# Gas_leakage.net
KiCad netlist of a schematic drawn in Altium Designer
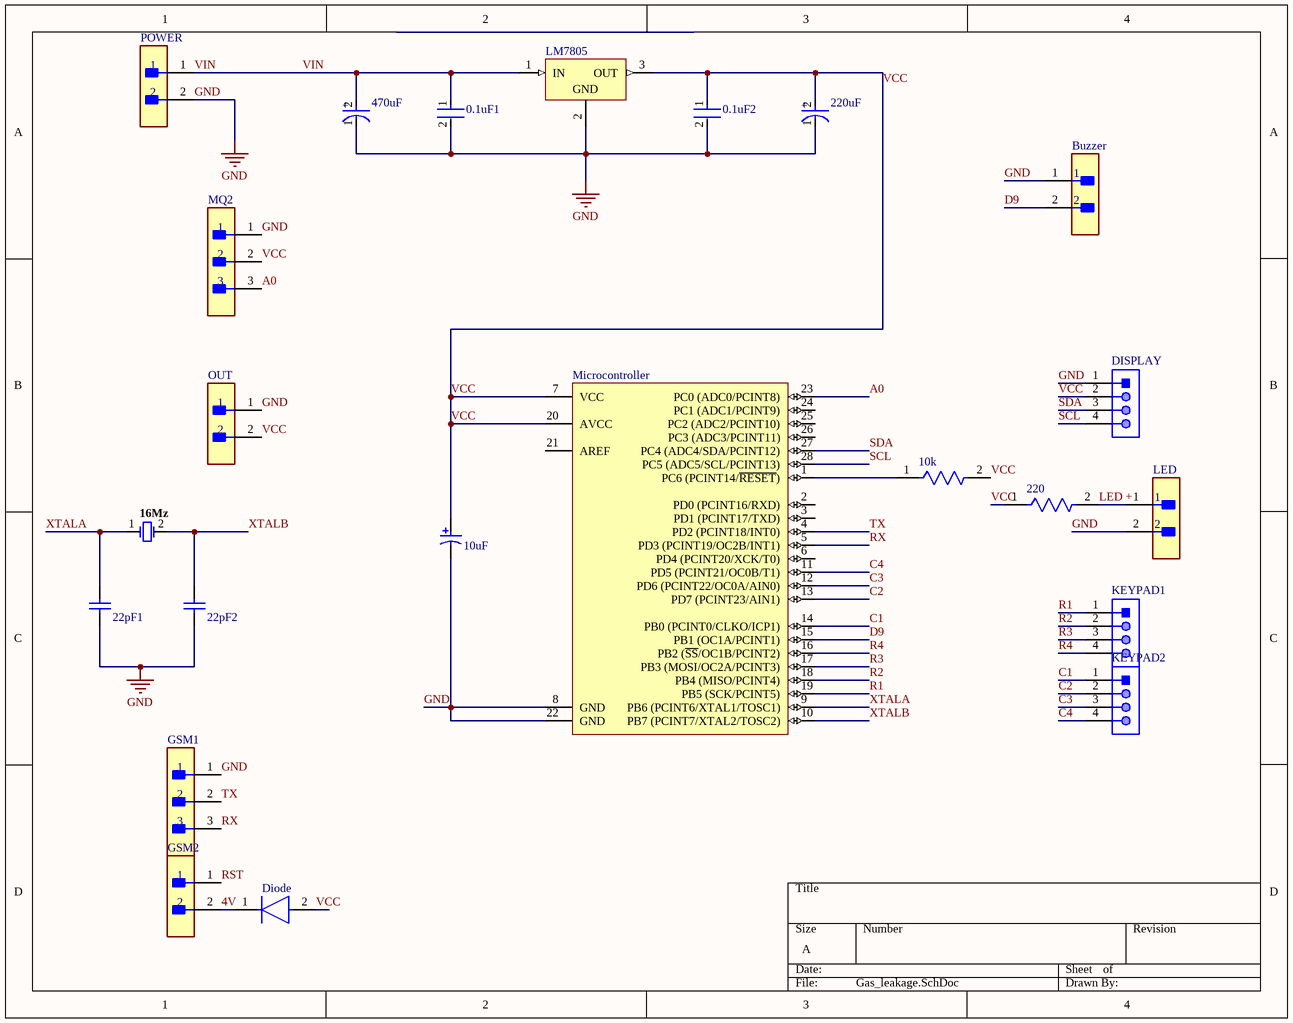
[diagram p0: Gas_leakage.SchDoc]

(export (version "E")
  (design (tool "Eeschema 10.0.6"))
  (components
    (comp (ref "0.1uF1")
      (value "SR205C104KAR")
      (footprint "FP-SR20-MFG")
      (description "CAP CER 0.1UF 50V X7R RADIAL")
      (fields (field (name "VOLTAGE") "50V") (field (name "TOLERANCE") "10%"))
      (libsource (lib "Altium Content Vault") (part "11868f565c42a9108669ba33697ecf6"))
    )
    (comp (ref "0.1uF2")
      (value "SR205C104KAR")
      (footprint "FP-SR20-MFG")
      (description "CAP CER 0.1UF 50V X7R RADIAL")
      (fields (field (name "VOLTAGE") "50V") (field (name "TOLERANCE") "10%"))
      (libsource (lib "Altium Content Vault") (part "11868f565c42a9108669ba33697ecf6"))
    )
    (comp (ref "10k")
      (value "CF18JT10K0")
      (footprint "FP-CF18-MFG")
      (description "RES 10K OHM 1/8W 5% CF AXIAL")
      (fields
        (field (name "MANUFACTURER") "Stackpole Electronics")
        (field (name "OCTOPART") "https://octopart.com/cf18jt10k0-stackpole+electronics-19205642")
      )
      (libsource (lib "Altium Content Vault") (part "1029c3af85768c4190bb7ad29bc67b5"))
    )
    (comp (ref "10uF")
      (value "ECA1HM100")
      (footprint "CAPPR55-200-1100X500X1200")
      (description "Aluminum Electrolytic Capacitor, 10 uF, +/- 20%, 50 V, -40 to 85 degC, 2-Pin THD, RoHS, Bulk")
      (fields (field (name "MANUFACTURER") "Panasonic") (field (name "TOLERANCE") "20%"))
      (libsource (lib "Altium Content Vault") (part "CAP-P-2"))
    )
    (comp (ref "16Mz")
      (value "FOXSLF/160-20")
      (footprint "FOX-FOXSLF160-20")
      (description "Resistance Weld Thru-Hole Crystal, 16 MHz, -20 to 70 degC, 2-Pin THD, RoHS, Bulk")
      (fields (field (name "TOLERANCE") "1%"))
      (libsource (lib "Altium Content Vault") (part "XTAL-1-2-2"))
    )
    (comp (ref "22pF1")
      (value "C315C220K1G5TA")
      (footprint "KEMT-C315-THT-2")
      (description "Capacitor, Ceramic, 22 pF, +/-10 %, 100 V, -55 to 125 degC, 2-Pin THD, RoHS, Bulk")
      (libsource (lib "Altium Content Vault") (part "CAP-NP-2"))
    )
    (comp (ref "22pF2")
      (value "C315C220K1G5TA")
      (footprint "KEMT-C315-THT-2")
      (description "Capacitor, Ceramic, 22 pF, +/-10 %, 100 V, -55 to 125 degC, 2-Pin THD, RoHS, Bulk")
      (libsource (lib "Altium Content Vault") (part "CAP-NP-2"))
    )
    (comp (ref "220")
      (value "CMF55205R00FHEB")
      (footprint "FP-CMF55-MFG")
      (description "RES 220 OHM 1/2W 1% AXIAL")
      (fields (field (name "TOLERANCE") "1%"))
      (libsource (lib "Altium Content Vault") (part "1029c3af85768c4190bb7ad29bc67b5"))
    )
    (comp (ref "220uF")
      (value "EEUFM1A221")
      (footprint "FP-RAD-TH-D_6_3_0_5-L_11-MFG")
      (description "Aluminum Electrolytic Capacitors (Radial Lead Type) 220uF ±20% 10V")
      (fields (field (name "VOLTAGE") "10V") (field (name "TOLERANCE") "20%"))
      (libsource (lib "Altium Content Vault") (part "a00bbbee19879c290e62620ae7e47b1"))
    )
    (comp (ref "470uF")
      (value "EEUHD1E471")
      (footprint "FP-RAD-TH-D_10_0_5-L_12_5-MFG")
      (description "Aluminum Electrolytic Capacitors (Radial Lead Type) AEC-Q200 Qualified 470uF ±20% 25V")
      (fields (field (name "TOLERANCE") "20%") (field (name "VOLTAGE") "25V"))
      (libsource (lib "Altium Content Vault") (part "203bc49f2ac43e59fd269a8c329ed05"))
    )
    (comp (ref "Buzzer")
      (value "M20-9990246")
      (footprint "FP-M20-9990246-MFG")
      (description "CONN HEADER VERT 2POS 2.54MM")
      (fields
        (field (name "OCTOPART") "https://octopart.com/m20-9990246-harwin-2590635")
        (field (name "MANUFACTURER") "Harwin")
      )
      (libsource (lib "") (part "3bc925449376181038e59eaffc5286c_1"))
    )
    (comp (ref "Diode")
      (value "1N5408G-T")
      (footprint "FP-DO-201AD-MFG")
      (description "DIODE GEN PURP 1KV 3A DO201AD")
      (libsource (lib "Altium Content Vault") (part "d7152d700b627762746794eb795d46e"))
    )
    (comp (ref "DISPLAY")
      (value "61300411121")
      (footprint "61300411121")
      (description "THT Vertical Pin Header WR-PHD, Pitch 2.54 mm, Single Row, 4 pins")
      (fields (field (name "MANUFACTURER") "Wurth Elektronik") (field (name "PUBLISHER") "WurthElektronik"))
      (libsource (lib "Altium Content Vault") (part "WE-CN-1P-M-R4"))
    )
    (comp (ref "GSM1")
      (value "90120-0763")
      (footprint "FP-90120-0763-MFG")
      (description "CONN HEADER VERT 3POS 2.54MM")
      (fields
        (field (name "MANUFACTURER") "Molex")
        (field (name "OCTOPART") "https://octopart.com/90120-0763-molex-655433")
      )
      (libsource (lib "Altium Content Vault") (part "0d3f023dd272f625e17a2be33dea85f"))
    )
    (comp (ref "GSM2")
      (value "M20-9990246")
      (footprint "FP-M20-9990246-MFG")
      (description "CONN HEADER VERT 2POS 2.54MM")
      (fields
        (field (name "OCTOPART") "https://octopart.com/m20-9990246-harwin-2590635")
        (field (name "MANUFACTURER") "Harwin")
      )
      (libsource (lib "Altium Content Vault") (part "3bc925449376181038e59eaffc5286c"))
    )
    (comp (ref "KEYPAD1")
      (value "1300411121")
      (footprint "61300411121")
      (description "THT Vertical Pin Header WR-PHD, Pitch 2.54 mm, Single Row, 4 pins")
      (fields
        (field (name "MANUFACTURER") "Wurth Elektronik")
        (field (name "PART NUMBER") "61300411121")
        (field (name "PUBLISHER") "WurthElektronik")
      )
      (libsource (lib "Altium Content Vault") (part "WE-CN-1P-M-R4"))
    )
    (comp (ref "KEYPAD2")
      (value "61300411121")
      (footprint "61300411121")
      (description "THT Vertical Pin Header WR-PHD, Pitch 2.54 mm, Single Row, 4 pins")
      (fields (field (name "MANUFACTURER") "Wurth Elektronik") (field (name "PUBLISHER") "WurthElektronik"))
      (libsource (lib "Altium Content Vault") (part "WE-CN-1P-M-R4"))
    )
    (comp (ref "LED")
      (value "M20-9990246")
      (footprint "FP-M20-9990246-MFG")
      (description "CONN HEADER VERT 2POS 2.54MM")
      (fields
        (field (name "OCTOPART") "https://octopart.com/m20-9990246-harwin-2590635")
        (field (name "MANUFACTURER") "Harwin")
      )
      (libsource (lib "") (part "3bc925449376181038e59eaffc5286c_1"))
    )
    (comp (ref "LM7805")
      (value "LM7805CT")
      (footprint "FAIR-TO-220-3")
      (description "Positive Voltage Regulator, 5 V, 1 A, -40 to 125 degC, 3-Pin TO-220, RoHS, Tube")
      (fields (field (name "MANUFACTURER") "FairchildSemiconductor"))
      (libsource (lib "Altium Content Vault") (part "FAIR-LM7805CT-TO220-3"))
    )
    (comp (ref "Microcontroller")
      (value "ATmega328P-PU")
      (footprint "28P3")
      (libsource (lib "Altium Content Vault") (part "MC-8B-ATM48-IL28"))
    )
    (comp (ref "MQ2")
      (value "90120-0763")
      (footprint "FP-90120-0763-MFG")
      (description "CONN HEADER VERT 3POS 2.54MM")
      (fields
        (field (name "MANUFACTURER") "Molex")
        (field (name "OCTOPART") "https://octopart.com/90120-0763-molex-655433")
      )
      (libsource (lib "Altium Content Vault") (part "0d3f023dd272f625e17a2be33dea85f"))
    )
    (comp (ref "OUT")
      (value "M20-9990246")
      (footprint "FP-M20-9990246-MFG")
      (description "CONN HEADER VERT 2POS 2.54MM")
      (fields
        (field (name "OCTOPART") "https://octopart.com/m20-9990246-harwin-2590635")
        (field (name "MANUFACTURER") "Harwin")
      )
      (libsource (lib "Altium Content Vault") (part "3bc925449376181038e59eaffc5286c"))
    )
    (comp (ref "POWER")
      (value "M20-9990246")
      (footprint "FP-M20-9990246-MFG")
      (description "CONN HEADER VERT 2POS 2.54MM")
      (fields
        (field (name "OCTOPART") "https://octopart.com/m20-9990246-harwin-2590635")
        (field (name "MANUFACTURER") "Harwin")
      )
      (libsource (lib "Altium Content Vault") (part "3bc925449376181038e59eaffc5286c"))
    )
  )
  (nets
    (net (code "1") (name "/4V") (class "Default")
      (node (ref "Diode") (pin "1") (pinfunction "C_1") (pintype "passive"))
      (node (ref "GSM2") (pin "2") (pinfunction "2_2") (pintype "passive"))
    )
    (net (code "2") (name "/A0") (class "Default")
      (node (ref "MQ2") (pin "3") (pinfunction "3_3") (pintype "passive"))
      (node (ref "Microcontroller") (pin "23") (pinfunction "PC0_(ADC0/PCINT8)_23") (pintype "bidirectional"))
    )
    (net (code "3") (name "/C1") (class "Default")
      (node (ref "KEYPAD2") (pin "1") (pinfunction "1_1") (pintype "passive"))
      (node (ref "Microcontroller") (pin "14") (pinfunction "PB0_(PCINT0/CLKO/ICP1)_14") (pintype "bidirectional"))
    )
    (net (code "4") (name "/C2") (class "Default")
      (node (ref "KEYPAD2") (pin "2") (pinfunction "2_2") (pintype "passive"))
      (node (ref "Microcontroller") (pin "13") (pinfunction "PD7_(PCINT23/AIN1)_13") (pintype "bidirectional"))
    )
    (net (code "5") (name "/C3") (class "Default")
      (node (ref "KEYPAD2") (pin "3") (pinfunction "3_3") (pintype "passive"))
      (node (ref "Microcontroller") (pin "12") (pinfunction "PD6_(PCINT22/OC0A/AIN0)_12") (pintype "bidirectional"))
    )
    (net (code "6") (name "/C4") (class "Default")
      (node (ref "KEYPAD2") (pin "4") (pinfunction "4_4") (pintype "passive"))
      (node (ref "Microcontroller") (pin "11") (pinfunction "PD5_(PCINT21/OC0B/T1)_11") (pintype "bidirectional"))
    )
    (net (code "7") (name "/D9") (class "Default")
      (node (ref "Buzzer") (pin "2") (pinfunction "2_2") (pintype "passive"))
      (node (ref "Microcontroller") (pin "15") (pinfunction "PB1_(OC1A/PCINT1)_15") (pintype "bidirectional"))
    )
    (net (code "8") (name "/LED +") (class "Default")
      (node (ref "220") (pin "2") (pinfunction "2_2") (pintype "passive"))
      (node (ref "LED") (pin "1") (pinfunction "1_1") (pintype "passive"))
    )
    (net (code "9") (name "/R1") (class "Default")
      (node (ref "KEYPAD1") (pin "1") (pinfunction "1_1") (pintype "passive"))
      (node (ref "Microcontroller") (pin "19") (pinfunction "PB5_(SCK/PCINT5)_19") (pintype "bidirectional"))
    )
    (net (code "10") (name "/R2") (class "Default")
      (node (ref "KEYPAD1") (pin "2") (pinfunction "2_2") (pintype "passive"))
      (node (ref "Microcontroller") (pin "18") (pinfunction "PB4_(MISO/PCINT4)_18") (pintype "bidirectional"))
    )
    (net (code "11") (name "/R3") (class "Default")
      (node (ref "KEYPAD1") (pin "3") (pinfunction "3_3") (pintype "passive"))
      (node (ref "Microcontroller") (pin "17") (pinfunction "PB3_(MOSI/OC2A/PCINT3)_17") (pintype "bidirectional"))
    )
    (net (code "12") (name "/R4") (class "Default")
      (node (ref "KEYPAD1") (pin "4") (pinfunction "4_4") (pintype "passive"))
      (node (ref "Microcontroller") (pin "16") (pinfunction "PB2_(~{SS}/OC1B/PCINT2)_16") (pintype "bidirectional"))
    )
    (net (code "13") (name "/RST") (class "Default")
      (node (ref "GSM2") (pin "1") (pinfunction "1_1") (pintype "passive"))
    )
    (net (code "14") (name "/RX") (class "Default")
      (node (ref "GSM1") (pin "3") (pinfunction "3_3") (pintype "passive"))
      (node (ref "Microcontroller") (pin "5") (pinfunction "PD3_(PCINT19/OC2B/INT1)_5") (pintype "bidirectional"))
    )
    (net (code "15") (name "/SCL") (class "Default")
      (node (ref "DISPLAY") (pin "4") (pinfunction "4_4") (pintype "passive"))
      (node (ref "Microcontroller") (pin "28") (pinfunction "PC5_(ADC5/SCL/PCINT13)_28") (pintype "bidirectional"))
    )
    (net (code "16") (name "/SDA") (class "Default")
      (node (ref "DISPLAY") (pin "3") (pinfunction "3_3") (pintype "passive"))
      (node (ref "Microcontroller") (pin "27") (pinfunction "PC4_(ADC4/SDA/PCINT12)_27") (pintype "bidirectional"))
    )
    (net (code "17") (name "/TX") (class "Default")
      (node (ref "GSM1") (pin "2") (pinfunction "2_2") (pintype "passive"))
      (node (ref "Microcontroller") (pin "4") (pinfunction "PD2_(PCINT18/INT0)_4") (pintype "bidirectional"))
    )
    (net (code "18") (name "/VCC") (class "Default")
      (node (ref "0.1uF2") (pin "1") (pinfunction "1_1") (pintype "passive"))
      (node (ref "10k") (pin "2") (pinfunction "2_2") (pintype "passive"))
      (node (ref "10uF") (pin "1") (pinfunction "1_1") (pintype "passive"))
      (node (ref "220") (pin "1") (pinfunction "1_1") (pintype "passive"))
      (node (ref "220uF") (pin "2") (pinfunction "A_2") (pintype "passive"))
      (node (ref "DISPLAY") (pin "2") (pinfunction "2_2") (pintype "passive"))
      (node (ref "Diode") (pin "2") (pinfunction "A_2") (pintype "passive"))
      (node (ref "LM7805") (pin "3") (pinfunction "OUT_3") (pintype "output"))
      (node (ref "MQ2") (pin "2") (pinfunction "2_2") (pintype "passive"))
      (node (ref "Microcontroller") (pin "20") (pinfunction "AVCC_20") (pintype "power_in"))
      (node (ref "Microcontroller") (pin "7") (pinfunction "VCC_7") (pintype "power_in"))
      (node (ref "OUT") (pin "2") (pinfunction "2_2") (pintype "passive"))
    )
    (net (code "19") (name "/VIN") (class "Default")
      (node (ref "0.1uF1") (pin "1") (pinfunction "1_1") (pintype "passive"))
      (node (ref "470uF") (pin "2") (pinfunction "A_2") (pintype "passive"))
      (node (ref "LM7805") (pin "1") (pinfunction "IN_1") (pintype "input"))
      (node (ref "POWER") (pin "1") (pinfunction "1_1") (pintype "passive"))
    )
    (net (code "20") (name "/XTALA") (class "Default")
      (node (ref "16Mz") (pin "1") (pinfunction "1_1") (pintype "passive"))
      (node (ref "22pF1") (pin "2") (pinfunction "2_2") (pintype "passive"))
      (node (ref "Microcontroller") (pin "9") (pinfunction "PB6_(PCINT6/XTAL1/TOSC1)_9") (pintype "bidirectional"))
    )
    (net (code "21") (name "/XTALB") (class "Default")
      (node (ref "16Mz") (pin "2") (pinfunction "2_2") (pintype "passive"))
      (node (ref "22pF2") (pin "2") (pinfunction "2_2") (pintype "passive"))
      (node (ref "Microcontroller") (pin "10") (pinfunction "PB7_(PCINT7/XTAL2/TOSC2)_10") (pintype "bidirectional"))
    )
    (net (code "22") (name "GND") (class "Default")
      (node (ref "0.1uF1") (pin "2") (pinfunction "2_2") (pintype "passive"))
      (node (ref "0.1uF2") (pin "2") (pinfunction "2_2") (pintype "passive"))
      (node (ref "10uF") (pin "2") (pinfunction "2_2") (pintype "passive"))
      (node (ref "220uF") (pin "1") (pinfunction "C_1") (pintype "passive"))
      (node (ref "22pF1") (pin "1") (pinfunction "1_1") (pintype "passive"))
      (node (ref "22pF2") (pin "1") (pinfunction "1_1") (pintype "passive"))
      (node (ref "470uF") (pin "1") (pinfunction "C_1") (pintype "passive"))
      (node (ref "Buzzer") (pin "1") (pinfunction "1_1") (pintype "passive"))
      (node (ref "DISPLAY") (pin "1") (pinfunction "1_1") (pintype "passive"))
      (node (ref "GSM1") (pin "1") (pinfunction "1_1") (pintype "passive"))
      (node (ref "LED") (pin "2") (pinfunction "2_2") (pintype "passive"))
      (node (ref "LM7805") (pin "2") (pinfunction "GND_2") (pintype "power_in"))
      (node (ref "MQ2") (pin "1") (pinfunction "1_1") (pintype "passive"))
      (node (ref "Microcontroller") (pin "22") (pinfunction "GND_22") (pintype "power_in"))
      (node (ref "Microcontroller") (pin "8") (pinfunction "GND_8") (pintype "power_in"))
      (node (ref "OUT") (pin "1") (pinfunction "1_1") (pintype "passive"))
      (node (ref "POWER") (pin "2") (pinfunction "2_2") (pintype "passive"))
    )
    (net (code "23") (name "Net-(Microcontroller-PC6_(PCINT14{slash}~{RESET}))") (class "Default")
      (node (ref "10k") (pin "1") (pinfunction "1_1") (pintype "passive"))
      (node (ref "Microcontroller") (pin "1") (pinfunction "PC6_(PCINT14/~{RESET})_1") (pintype "bidirectional"))
    )
    (net (code "24") (name "unconnected-(Microcontroller-AREF-Pad21)") (class "Default")
      (node (ref "Microcontroller") (pin "21") (pinfunction "AREF_21") (pintype "power_in"))
    )
    (net (code "25") (name "unconnected-(Microcontroller-PC1_(ADC1{slash}PCINT9)-Pad24)") (class "Default")
      (node (ref "Microcontroller") (pin "24") (pinfunction "PC1_(ADC1/PCINT9)_24") (pintype "bidirectional"))
    )
    (net (code "26") (name "unconnected-(Microcontroller-PC2_(ADC2{slash}PCINT10)-Pad25)") (class "Default")
      (node (ref "Microcontroller") (pin "25") (pinfunction "PC2_(ADC2/PCINT10)_25") (pintype "bidirectional"))
    )
    (net (code "27") (name "unconnected-(Microcontroller-PC3_(ADC3{slash}PCINT11)-Pad26)") (class "Default")
      (node (ref "Microcontroller") (pin "26") (pinfunction "PC3_(ADC3/PCINT11)_26") (pintype "bidirectional"))
    )
    (net (code "28") (name "unconnected-(Microcontroller-PD0_(PCINT16{slash}RXD)-Pad2)") (class "Default")
      (node (ref "Microcontroller") (pin "2") (pinfunction "PD0_(PCINT16/RXD)_2") (pintype "bidirectional"))
    )
    (net (code "29") (name "unconnected-(Microcontroller-PD1_(PCINT17{slash}TXD)-Pad3)") (class "Default")
      (node (ref "Microcontroller") (pin "3") (pinfunction "PD1_(PCINT17/TXD)_3") (pintype "bidirectional"))
    )
    (net (code "30") (name "unconnected-(Microcontroller-PD4_(PCINT20{slash}XCK{slash}T0)-Pad6)") (class "Default")
      (node (ref "Microcontroller") (pin "6") (pinfunction "PD4_(PCINT20/XCK/T0)_6") (pintype "bidirectional"))
    )
  )
)
